# Steppers.net
KiCad netlist of a schematic drawn in Altium Designer
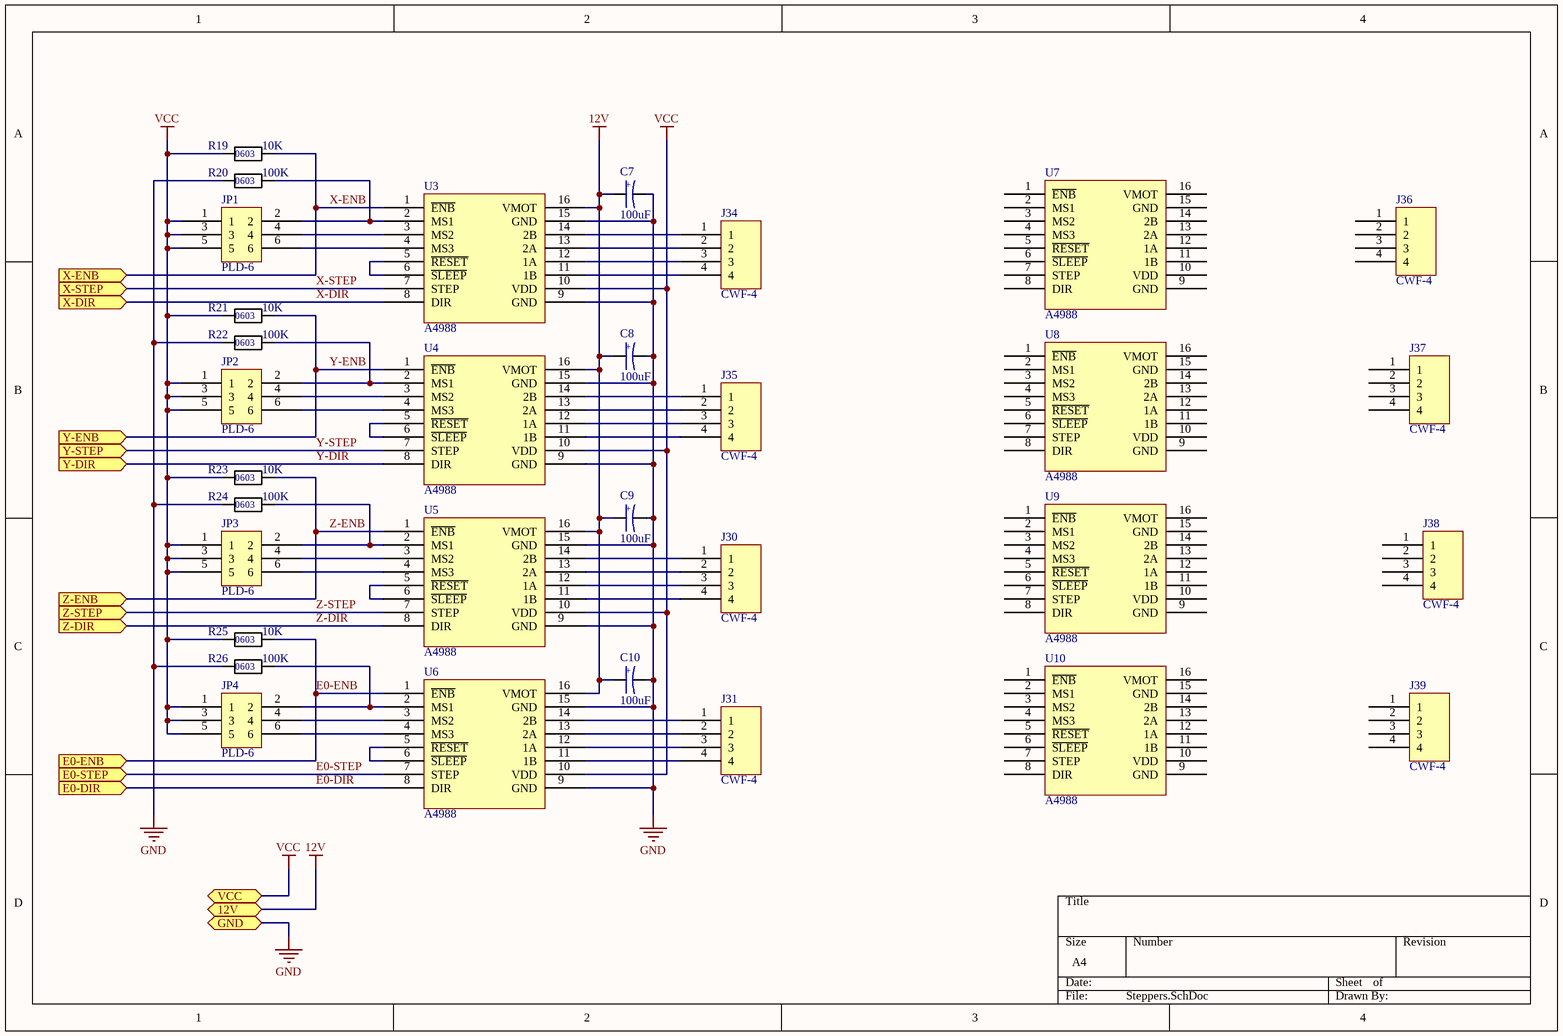
[diagram p0: Steppers.SchDoc]

(export (version "E")
  (design (tool "Eeschema 10.0.6"))
  (components
    (comp (ref "C7") (value "100uF") (footprint "Tantal - D") (libsource (lib "Popular") (part "Tantal")))
    (comp (ref "C8") (value "100uF") (footprint "Tantal - D") (libsource (lib "Popular") (part "Tantal")))
    (comp (ref "C9") (value "100uF") (footprint "Tantal - D") (libsource (lib "Popular") (part "Tantal")))
    (comp (ref "C10") (value "100uF") (footprint "Tantal - D") (libsource (lib "Popular") (part "Tantal")))
    (comp (ref "J30") (value "CWF-4") (footprint "CWF-4") (libsource (lib "Popular") (part "CWF-4")))
    (comp (ref "J31") (value "CWF-4") (footprint "CWF-4") (libsource (lib "Popular") (part "CWF-4")))
    (comp (ref "J34") (value "CWF-4") (footprint "CWF-4") (libsource (lib "Popular") (part "CWF-4")))
    (comp (ref "J35") (value "CWF-4") (footprint "CWF-4") (libsource (lib "Popular") (part "CWF-4")))
    (comp (ref "J36") (value "CWF-4") (footprint "CWF-4") (libsource (lib "Popular") (part "CWF-4")))
    (comp (ref "J37") (value "CWF-4") (footprint "CWF-4") (libsource (lib "Popular") (part "CWF-4")))
    (comp (ref "J38") (value "CWF-4") (footprint "CWF-4") (libsource (lib "Popular") (part "CWF-4")))
    (comp (ref "J39") (value "CWF-4") (footprint "CWF-4") (libsource (lib "Popular") (part "CWF-4")))
    (comp (ref "JP1") (value "PLD-6") (footprint "PLD-6") (libsource (lib "Popular") (part "PLD-6")))
    (comp (ref "JP2") (value "PLD-6") (footprint "PLD-6") (libsource (lib "Popular") (part "PLD-6")))
    (comp (ref "JP3") (value "PLD-6") (footprint "PLD-6") (libsource (lib "Popular") (part "PLD-6")))
    (comp (ref "JP4") (value "PLD-6") (footprint "PLD-6") (libsource (lib "Popular") (part "PLD-6")))
    (comp (ref "R19") (value "10K") (footprint "CHIP_R_0603") (libsource (lib "Popular") (part "RES_0603")))
    (comp (ref "R20") (value "100K") (footprint "CHIP_R_0603") (libsource (lib "Popular") (part "RES_0603")))
    (comp (ref "R21") (value "10K") (footprint "CHIP_R_0603") (libsource (lib "Popular") (part "RES_0603")))
    (comp (ref "R22") (value "100K") (footprint "CHIP_R_0603") (libsource (lib "Popular") (part "RES_0603")))
    (comp (ref "R23") (value "10K") (footprint "CHIP_R_0603") (libsource (lib "Popular") (part "RES_0603")))
    (comp (ref "R24") (value "100K") (footprint "CHIP_R_0603") (libsource (lib "Popular") (part "RES_0603")))
    (comp (ref "R25") (value "10K") (footprint "CHIP_R_0603") (libsource (lib "Popular") (part "RES_0603")))
    (comp (ref "R26") (value "100K") (footprint "CHIP_R_0603") (libsource (lib "Popular") (part "RES_0603")))
    (comp (ref "U3") (value "A4988") (footprint "A4988") (libsource (lib "Popular") (part "A4988_Carrier")))
    (comp (ref "U4") (value "A4988") (footprint "A4988") (libsource (lib "Popular") (part "A4988_Carrier")))
    (comp (ref "U5") (value "A4988") (footprint "A4988") (libsource (lib "Popular") (part "A4988_Carrier")))
    (comp (ref "U6") (value "A4988") (footprint "A4988") (libsource (lib "Popular") (part "A4988_Carrier")))
    (comp (ref "U7") (value "A4988") (footprint "A4988") (libsource (lib "Popular") (part "A4988_Carrier")))
    (comp (ref "U8") (value "A4988") (footprint "A4988") (libsource (lib "Popular") (part "A4988_Carrier")))
    (comp (ref "U9") (value "A4988") (footprint "A4988") (libsource (lib "Popular") (part "A4988_Carrier")))
    (comp (ref "U10") (value "A4988") (footprint "A4988") (libsource (lib "Popular") (part "A4988_Carrier")))
  )
  (nets
    (net (code "1") (name "/E0-DIR") (class "Default")
      (node (ref "U6") (pin "8") (pinfunction "DIR_8") (pintype "passive"))
    )
    (net (code "2") (name "/E0-ENB") (class "Default")
      (node (ref "R25") (pin "2") (pinfunction "2_2") (pintype "passive"))
      (node (ref "U6") (pin "1") (pinfunction "~{ENB}_1") (pintype "passive"))
    )
    (net (code "3") (name "/E0-STEP") (class "Default")
      (node (ref "U6") (pin "7") (pinfunction "STEP_7") (pintype "passive"))
    )
    (net (code "4") (name "/X-DIR") (class "Default")
      (node (ref "U3") (pin "8") (pinfunction "DIR_8") (pintype "passive"))
    )
    (net (code "5") (name "/X-ENB") (class "Default")
      (node (ref "R19") (pin "2") (pinfunction "2_2") (pintype "passive"))
      (node (ref "U3") (pin "1") (pinfunction "~{ENB}_1") (pintype "passive"))
    )
    (net (code "6") (name "/X-STEP") (class "Default")
      (node (ref "U3") (pin "7") (pinfunction "STEP_7") (pintype "passive"))
    )
    (net (code "7") (name "/Y-DIR") (class "Default")
      (node (ref "U4") (pin "8") (pinfunction "DIR_8") (pintype "passive"))
    )
    (net (code "8") (name "/Y-ENB") (class "Default")
      (node (ref "R21") (pin "2") (pinfunction "2_2") (pintype "passive"))
      (node (ref "U4") (pin "1") (pinfunction "~{ENB}_1") (pintype "passive"))
    )
    (net (code "9") (name "/Y-STEP") (class "Default")
      (node (ref "U4") (pin "7") (pinfunction "STEP_7") (pintype "passive"))
    )
    (net (code "10") (name "/Z-DIR") (class "Default")
      (node (ref "U5") (pin "8") (pinfunction "DIR_8") (pintype "passive"))
    )
    (net (code "11") (name "/Z-ENB") (class "Default")
      (node (ref "R23") (pin "2") (pinfunction "2_2") (pintype "passive"))
      (node (ref "U5") (pin "1") (pinfunction "~{ENB}_1") (pintype "passive"))
    )
    (net (code "12") (name "/Z-STEP") (class "Default")
      (node (ref "U5") (pin "7") (pinfunction "STEP_7") (pintype "passive"))
    )
    (net (code "13") (name "12V") (class "Default")
      (node (ref "C10") (pin "1") (pinfunction "1_1") (pintype "passive"))
      (node (ref "C7") (pin "1") (pinfunction "1_1") (pintype "passive"))
      (node (ref "C8") (pin "1") (pinfunction "1_1") (pintype "passive"))
      (node (ref "C9") (pin "1") (pinfunction "1_1") (pintype "passive"))
      (node (ref "U3") (pin "16") (pinfunction "VMOT_16") (pintype "passive"))
      (node (ref "U4") (pin "16") (pinfunction "VMOT_16") (pintype "passive"))
      (node (ref "U5") (pin "16") (pinfunction "VMOT_16") (pintype "passive"))
      (node (ref "U6") (pin "16") (pinfunction "VMOT_16") (pintype "passive"))
    )
    (net (code "14") (name "GND") (class "Default")
      (node (ref "C10") (pin "2") (pinfunction "2_2") (pintype "passive"))
      (node (ref "C7") (pin "2") (pinfunction "2_2") (pintype "passive"))
      (node (ref "C8") (pin "2") (pinfunction "2_2") (pintype "passive"))
      (node (ref "C9") (pin "2") (pinfunction "2_2") (pintype "passive"))
      (node (ref "R20") (pin "1") (pinfunction "1_1") (pintype "passive"))
      (node (ref "R22") (pin "1") (pinfunction "1_1") (pintype "passive"))
      (node (ref "R24") (pin "1") (pinfunction "1_1") (pintype "passive"))
      (node (ref "R26") (pin "1") (pinfunction "1_1") (pintype "passive"))
      (node (ref "U3") (pin "15") (pinfunction "GND_15") (pintype "passive"))
      (node (ref "U3") (pin "9") (pinfunction "GND_9") (pintype "passive"))
      (node (ref "U4") (pin "15") (pinfunction "GND_15") (pintype "passive"))
      (node (ref "U4") (pin "9") (pinfunction "GND_9") (pintype "passive"))
      (node (ref "U5") (pin "15") (pinfunction "GND_15") (pintype "passive"))
      (node (ref "U5") (pin "9") (pinfunction "GND_9") (pintype "passive"))
      (node (ref "U6") (pin "15") (pinfunction "GND_15") (pintype "passive"))
      (node (ref "U6") (pin "9") (pinfunction "GND_9") (pintype "passive"))
    )
    (net (code "15") (name "Net-(U3-1A)") (class "Default")
      (node (ref "J34") (pin "3") (pinfunction "3_3") (pintype "passive"))
      (node (ref "U3") (pin "12") (pinfunction "1A_12") (pintype "passive"))
    )
    (net (code "16") (name "Net-(U3-1B)") (class "Default")
      (node (ref "J34") (pin "4") (pinfunction "4_4") (pintype "passive"))
      (node (ref "U3") (pin "11") (pinfunction "1B_11") (pintype "passive"))
    )
    (net (code "17") (name "Net-(U3-2A)") (class "Default")
      (node (ref "J34") (pin "2") (pinfunction "2_2") (pintype "passive"))
      (node (ref "U3") (pin "13") (pinfunction "2A_13") (pintype "passive"))
    )
    (net (code "18") (name "Net-(U3-2B)") (class "Default")
      (node (ref "J34") (pin "1") (pinfunction "1_1") (pintype "passive"))
      (node (ref "U3") (pin "14") (pinfunction "2B_14") (pintype "passive"))
    )
    (net (code "19") (name "Net-(U3-MS1)") (class "Default")
      (node (ref "JP1") (pin "2") (pinfunction "2_2") (pintype "passive"))
      (node (ref "R20") (pin "2") (pinfunction "2_2") (pintype "passive"))
      (node (ref "U3") (pin "2") (pinfunction "MS1_2") (pintype "passive"))
    )
    (net (code "20") (name "Net-(U3-MS2)") (class "Default")
      (node (ref "JP1") (pin "4") (pinfunction "4_4") (pintype "passive"))
      (node (ref "U3") (pin "3") (pinfunction "MS2_3") (pintype "passive"))
    )
    (net (code "21") (name "Net-(U3-MS3)") (class "Default")
      (node (ref "JP1") (pin "6") (pinfunction "6_6") (pintype "passive"))
      (node (ref "U3") (pin "4") (pinfunction "MS3_4") (pintype "passive"))
    )
    (net (code "22") (name "Net-(U3-~{RESET})") (class "Default")
      (node (ref "U3") (pin "5") (pinfunction "~{RESET}_5") (pintype "passive"))
      (node (ref "U3") (pin "6") (pinfunction "~{SLEEP}_6") (pintype "passive"))
    )
    (net (code "23") (name "Net-(U4-1A)") (class "Default")
      (node (ref "J35") (pin "3") (pinfunction "3_3") (pintype "passive"))
      (node (ref "U4") (pin "12") (pinfunction "1A_12") (pintype "passive"))
    )
    (net (code "24") (name "Net-(U4-1B)") (class "Default")
      (node (ref "J35") (pin "4") (pinfunction "4_4") (pintype "passive"))
      (node (ref "U4") (pin "11") (pinfunction "1B_11") (pintype "passive"))
    )
    (net (code "25") (name "Net-(U4-2A)") (class "Default")
      (node (ref "J35") (pin "2") (pinfunction "2_2") (pintype "passive"))
      (node (ref "U4") (pin "13") (pinfunction "2A_13") (pintype "passive"))
    )
    (net (code "26") (name "Net-(U4-2B)") (class "Default")
      (node (ref "J35") (pin "1") (pinfunction "1_1") (pintype "passive"))
      (node (ref "U4") (pin "14") (pinfunction "2B_14") (pintype "passive"))
    )
    (net (code "27") (name "Net-(U4-MS1)") (class "Default")
      (node (ref "JP2") (pin "2") (pinfunction "2_2") (pintype "passive"))
      (node (ref "R22") (pin "2") (pinfunction "2_2") (pintype "passive"))
      (node (ref "U4") (pin "2") (pinfunction "MS1_2") (pintype "passive"))
    )
    (net (code "28") (name "Net-(U4-MS2)") (class "Default")
      (node (ref "JP2") (pin "4") (pinfunction "4_4") (pintype "passive"))
      (node (ref "U4") (pin "3") (pinfunction "MS2_3") (pintype "passive"))
    )
    (net (code "29") (name "Net-(U4-MS3)") (class "Default")
      (node (ref "JP2") (pin "6") (pinfunction "6_6") (pintype "passive"))
      (node (ref "U4") (pin "4") (pinfunction "MS3_4") (pintype "passive"))
    )
    (net (code "30") (name "Net-(U4-~{RESET})") (class "Default")
      (node (ref "U4") (pin "5") (pinfunction "~{RESET}_5") (pintype "passive"))
      (node (ref "U4") (pin "6") (pinfunction "~{SLEEP}_6") (pintype "passive"))
    )
    (net (code "31") (name "Net-(U5-1A)") (class "Default")
      (node (ref "J30") (pin "3") (pinfunction "3_3") (pintype "passive"))
      (node (ref "U5") (pin "12") (pinfunction "1A_12") (pintype "passive"))
    )
    (net (code "32") (name "Net-(U5-1B)") (class "Default")
      (node (ref "J30") (pin "4") (pinfunction "4_4") (pintype "passive"))
      (node (ref "U5") (pin "11") (pinfunction "1B_11") (pintype "passive"))
    )
    (net (code "33") (name "Net-(U5-2A)") (class "Default")
      (node (ref "J30") (pin "2") (pinfunction "2_2") (pintype "passive"))
      (node (ref "U5") (pin "13") (pinfunction "2A_13") (pintype "passive"))
    )
    (net (code "34") (name "Net-(U5-2B)") (class "Default")
      (node (ref "J30") (pin "1") (pinfunction "1_1") (pintype "passive"))
      (node (ref "U5") (pin "14") (pinfunction "2B_14") (pintype "passive"))
    )
    (net (code "35") (name "Net-(U5-MS1)") (class "Default")
      (node (ref "JP3") (pin "2") (pinfunction "2_2") (pintype "passive"))
      (node (ref "R24") (pin "2") (pinfunction "2_2") (pintype "passive"))
      (node (ref "U5") (pin "2") (pinfunction "MS1_2") (pintype "passive"))
    )
    (net (code "36") (name "Net-(U5-MS2)") (class "Default")
      (node (ref "JP3") (pin "4") (pinfunction "4_4") (pintype "passive"))
      (node (ref "U5") (pin "3") (pinfunction "MS2_3") (pintype "passive"))
    )
    (net (code "37") (name "Net-(U5-MS3)") (class "Default")
      (node (ref "JP3") (pin "6") (pinfunction "6_6") (pintype "passive"))
      (node (ref "U5") (pin "4") (pinfunction "MS3_4") (pintype "passive"))
    )
    (net (code "38") (name "Net-(U5-~{RESET})") (class "Default")
      (node (ref "U5") (pin "5") (pinfunction "~{RESET}_5") (pintype "passive"))
      (node (ref "U5") (pin "6") (pinfunction "~{SLEEP}_6") (pintype "passive"))
    )
    (net (code "39") (name "Net-(U6-1A)") (class "Default")
      (node (ref "J31") (pin "3") (pinfunction "3_3") (pintype "passive"))
      (node (ref "U6") (pin "12") (pinfunction "1A_12") (pintype "passive"))
    )
    (net (code "40") (name "Net-(U6-1B)") (class "Default")
      (node (ref "J31") (pin "4") (pinfunction "4_4") (pintype "passive"))
      (node (ref "U6") (pin "11") (pinfunction "1B_11") (pintype "passive"))
    )
    (net (code "41") (name "Net-(U6-2A)") (class "Default")
      (node (ref "J31") (pin "2") (pinfunction "2_2") (pintype "passive"))
      (node (ref "U6") (pin "13") (pinfunction "2A_13") (pintype "passive"))
    )
    (net (code "42") (name "Net-(U6-2B)") (class "Default")
      (node (ref "J31") (pin "1") (pinfunction "1_1") (pintype "passive"))
      (node (ref "U6") (pin "14") (pinfunction "2B_14") (pintype "passive"))
    )
    (net (code "43") (name "Net-(U6-MS1)") (class "Default")
      (node (ref "JP4") (pin "2") (pinfunction "2_2") (pintype "passive"))
      (node (ref "R26") (pin "2") (pinfunction "2_2") (pintype "passive"))
      (node (ref "U6") (pin "2") (pinfunction "MS1_2") (pintype "passive"))
    )
    (net (code "44") (name "Net-(U6-MS2)") (class "Default")
      (node (ref "JP4") (pin "4") (pinfunction "4_4") (pintype "passive"))
      (node (ref "U6") (pin "3") (pinfunction "MS2_3") (pintype "passive"))
    )
    (net (code "45") (name "Net-(U6-MS3)") (class "Default")
      (node (ref "JP4") (pin "6") (pinfunction "6_6") (pintype "passive"))
      (node (ref "U6") (pin "4") (pinfunction "MS3_4") (pintype "passive"))
    )
    (net (code "46") (name "Net-(U6-~{RESET})") (class "Default")
      (node (ref "U6") (pin "5") (pinfunction "~{RESET}_5") (pintype "passive"))
      (node (ref "U6") (pin "6") (pinfunction "~{SLEEP}_6") (pintype "passive"))
    )
    (net (code "47") (name "VCC") (class "Default")
      (node (ref "JP1") (pin "1") (pinfunction "1_1") (pintype "passive"))
      (node (ref "JP1") (pin "3") (pinfunction "3_3") (pintype "passive"))
      (node (ref "JP1") (pin "5") (pinfunction "5_5") (pintype "passive"))
      (node (ref "JP2") (pin "1") (pinfunction "1_1") (pintype "passive"))
      (node (ref "JP2") (pin "3") (pinfunction "3_3") (pintype "passive"))
      (node (ref "JP2") (pin "5") (pinfunction "5_5") (pintype "passive"))
      (node (ref "JP3") (pin "1") (pinfunction "1_1") (pintype "passive"))
      (node (ref "JP3") (pin "3") (pinfunction "3_3") (pintype "passive"))
      (node (ref "JP3") (pin "5") (pinfunction "5_5") (pintype "passive"))
      (node (ref "JP4") (pin "1") (pinfunction "1_1") (pintype "passive"))
      (node (ref "JP4") (pin "3") (pinfunction "3_3") (pintype "passive"))
      (node (ref "JP4") (pin "5") (pinfunction "5_5") (pintype "passive"))
      (node (ref "R19") (pin "1") (pinfunction "1_1") (pintype "passive"))
      (node (ref "R21") (pin "1") (pinfunction "1_1") (pintype "passive"))
      (node (ref "R23") (pin "1") (pinfunction "1_1") (pintype "passive"))
      (node (ref "R25") (pin "1") (pinfunction "1_1") (pintype "passive"))
      (node (ref "U3") (pin "10") (pinfunction "VDD_10") (pintype "passive"))
      (node (ref "U4") (pin "10") (pinfunction "VDD_10") (pintype "passive"))
      (node (ref "U5") (pin "10") (pinfunction "VDD_10") (pintype "passive"))
      (node (ref "U6") (pin "10") (pinfunction "VDD_10") (pintype "passive"))
    )
    (net (code "48") (name "unconnected-(J36-Pad1)") (class "Default")
      (node (ref "J36") (pin "1") (pinfunction "1_1") (pintype "passive"))
    )
    (net (code "49") (name "unconnected-(J36-Pad2)") (class "Default")
      (node (ref "J36") (pin "2") (pinfunction "2_2") (pintype "passive"))
    )
    (net (code "50") (name "unconnected-(J36-Pad3)") (class "Default")
      (node (ref "J36") (pin "3") (pinfunction "3_3") (pintype "passive"))
    )
    (net (code "51") (name "unconnected-(J36-Pad4)") (class "Default")
      (node (ref "J36") (pin "4") (pinfunction "4_4") (pintype "passive"))
    )
    (net (code "52") (name "unconnected-(J37-Pad1)") (class "Default")
      (node (ref "J37") (pin "1") (pinfunction "1_1") (pintype "passive"))
    )
    (net (code "53") (name "unconnected-(J37-Pad2)") (class "Default")
      (node (ref "J37") (pin "2") (pinfunction "2_2") (pintype "passive"))
    )
    (net (code "54") (name "unconnected-(J37-Pad3)") (class "Default")
      (node (ref "J37") (pin "3") (pinfunction "3_3") (pintype "passive"))
    )
    (net (code "55") (name "unconnected-(J37-Pad4)") (class "Default")
      (node (ref "J37") (pin "4") (pinfunction "4_4") (pintype "passive"))
    )
    (net (code "56") (name "unconnected-(J38-Pad1)") (class "Default")
      (node (ref "J38") (pin "1") (pinfunction "1_1") (pintype "passive"))
    )
    (net (code "57") (name "unconnected-(J38-Pad2)") (class "Default")
      (node (ref "J38") (pin "2") (pinfunction "2_2") (pintype "passive"))
    )
    (net (code "58") (name "unconnected-(J38-Pad3)") (class "Default")
      (node (ref "J38") (pin "3") (pinfunction "3_3") (pintype "passive"))
    )
    (net (code "59") (name "unconnected-(J38-Pad4)") (class "Default")
      (node (ref "J38") (pin "4") (pinfunction "4_4") (pintype "passive"))
    )
    (net (code "60") (name "unconnected-(J39-Pad1)") (class "Default")
      (node (ref "J39") (pin "1") (pinfunction "1_1") (pintype "passive"))
    )
    (net (code "61") (name "unconnected-(J39-Pad2)") (class "Default")
      (node (ref "J39") (pin "2") (pinfunction "2_2") (pintype "passive"))
    )
    (net (code "62") (name "unconnected-(J39-Pad3)") (class "Default")
      (node (ref "J39") (pin "3") (pinfunction "3_3") (pintype "passive"))
    )
    (net (code "63") (name "unconnected-(J39-Pad4)") (class "Default")
      (node (ref "J39") (pin "4") (pinfunction "4_4") (pintype "passive"))
    )
    (net (code "64") (name "unconnected-(U7-1A-Pad12)") (class "Default")
      (node (ref "U7") (pin "12") (pinfunction "1A_12") (pintype "passive"))
    )
    (net (code "65") (name "unconnected-(U7-1B-Pad11)") (class "Default")
      (node (ref "U7") (pin "11") (pinfunction "1B_11") (pintype "passive"))
    )
    (net (code "66") (name "unconnected-(U7-2A-Pad13)") (class "Default")
      (node (ref "U7") (pin "13") (pinfunction "2A_13") (pintype "passive"))
    )
    (net (code "67") (name "unconnected-(U7-2B-Pad14)") (class "Default")
      (node (ref "U7") (pin "14") (pinfunction "2B_14") (pintype "passive"))
    )
    (net (code "68") (name "unconnected-(U7-DIR-Pad8)") (class "Default")
      (node (ref "U7") (pin "8") (pinfunction "DIR_8") (pintype "passive"))
    )
    (net (code "69") (name "unconnected-(U7-GND-Pad9)") (class "Default")
      (node (ref "U7") (pin "9") (pinfunction "GND_9") (pintype "passive"))
    )
    (net (code "70") (name "unconnected-(U7-GND-Pad15)") (class "Default")
      (node (ref "U7") (pin "15") (pinfunction "GND_15") (pintype "passive"))
    )
    (net (code "71") (name "unconnected-(U7-MS1-Pad2)") (class "Default")
      (node (ref "U7") (pin "2") (pinfunction "MS1_2") (pintype "passive"))
    )
    (net (code "72") (name "unconnected-(U7-MS2-Pad3)") (class "Default")
      (node (ref "U7") (pin "3") (pinfunction "MS2_3") (pintype "passive"))
    )
    (net (code "73") (name "unconnected-(U7-MS3-Pad4)") (class "Default")
      (node (ref "U7") (pin "4") (pinfunction "MS3_4") (pintype "passive"))
    )
    (net (code "74") (name "unconnected-(U7-STEP-Pad7)") (class "Default")
      (node (ref "U7") (pin "7") (pinfunction "STEP_7") (pintype "passive"))
    )
    (net (code "75") (name "unconnected-(U7-VDD-Pad10)") (class "Default")
      (node (ref "U7") (pin "10") (pinfunction "VDD_10") (pintype "passive"))
    )
    (net (code "76") (name "unconnected-(U7-VMOT-Pad16)") (class "Default")
      (node (ref "U7") (pin "16") (pinfunction "VMOT_16") (pintype "passive"))
    )
    (net (code "77") (name "unconnected-(U7-~{ENB}-Pad1)") (class "Default")
      (node (ref "U7") (pin "1") (pinfunction "~{ENB}_1") (pintype "passive"))
    )
    (net (code "78") (name "unconnected-(U7-~{RESET}-Pad5)") (class "Default")
      (node (ref "U7") (pin "5") (pinfunction "~{RESET}_5") (pintype "passive"))
    )
    (net (code "79") (name "unconnected-(U7-~{SLEEP}-Pad6)") (class "Default")
      (node (ref "U7") (pin "6") (pinfunction "~{SLEEP}_6") (pintype "passive"))
    )
    (net (code "80") (name "unconnected-(U8-1A-Pad12)") (class "Default")
      (node (ref "U8") (pin "12") (pinfunction "1A_12") (pintype "passive"))
    )
    (net (code "81") (name "unconnected-(U8-1B-Pad11)") (class "Default")
      (node (ref "U8") (pin "11") (pinfunction "1B_11") (pintype "passive"))
    )
    (net (code "82") (name "unconnected-(U8-2A-Pad13)") (class "Default")
      (node (ref "U8") (pin "13") (pinfunction "2A_13") (pintype "passive"))
    )
    (net (code "83") (name "unconnected-(U8-2B-Pad14)") (class "Default")
      (node (ref "U8") (pin "14") (pinfunction "2B_14") (pintype "passive"))
    )
    (net (code "84") (name "unconnected-(U8-DIR-Pad8)") (class "Default")
      (node (ref "U8") (pin "8") (pinfunction "DIR_8") (pintype "passive"))
    )
    (net (code "85") (name "unconnected-(U8-GND-Pad9)") (class "Default")
      (node (ref "U8") (pin "9") (pinfunction "GND_9") (pintype "passive"))
    )
    (net (code "86") (name "unconnected-(U8-GND-Pad15)") (class "Default")
      (node (ref "U8") (pin "15") (pinfunction "GND_15") (pintype "passive"))
    )
    (net (code "87") (name "unconnected-(U8-MS1-Pad2)") (class "Default")
      (node (ref "U8") (pin "2") (pinfunction "MS1_2") (pintype "passive"))
    )
    (net (code "88") (name "unconnected-(U8-MS2-Pad3)") (class "Default")
      (node (ref "U8") (pin "3") (pinfunction "MS2_3") (pintype "passive"))
    )
    (net (code "89") (name "unconnected-(U8-MS3-Pad4)") (class "Default")
      (node (ref "U8") (pin "4") (pinfunction "MS3_4") (pintype "passive"))
    )
    (net (code "90") (name "unconnected-(U8-STEP-Pad7)") (class "Default")
      (node (ref "U8") (pin "7") (pinfunction "STEP_7") (pintype "passive"))
    )
    (net (code "91") (name "unconnected-(U8-VDD-Pad10)") (class "Default")
      (node (ref "U8") (pin "10") (pinfunction "VDD_10") (pintype "passive"))
    )
    (net (code "92") (name "unconnected-(U8-VMOT-Pad16)") (class "Default")
      (node (ref "U8") (pin "16") (pinfunction "VMOT_16") (pintype "passive"))
    )
    (net (code "93") (name "unconnected-(U8-~{ENB}-Pad1)") (class "Default")
      (node (ref "U8") (pin "1") (pinfunction "~{ENB}_1") (pintype "passive"))
    )
    (net (code "94") (name "unconnected-(U8-~{RESET}-Pad5)") (class "Default")
      (node (ref "U8") (pin "5") (pinfunction "~{RESET}_5") (pintype "passive"))
    )
    (net (code "95") (name "unconnected-(U8-~{SLEEP}-Pad6)") (class "Default")
      (node (ref "U8") (pin "6") (pinfunction "~{SLEEP}_6") (pintype "passive"))
    )
    (net (code "96") (name "unconnected-(U9-1A-Pad12)") (class "Default")
      (node (ref "U9") (pin "12") (pinfunction "1A_12") (pintype "passive"))
    )
    (net (code "97") (name "unconnected-(U9-1B-Pad11)") (class "Default")
      (node (ref "U9") (pin "11") (pinfunction "1B_11") (pintype "passive"))
    )
    (net (code "98") (name "unconnected-(U9-2A-Pad13)") (class "Default")
      (node (ref "U9") (pin "13") (pinfunction "2A_13") (pintype "passive"))
    )
    (net (code "99") (name "unconnected-(U9-2B-Pad14)") (class "Default")
      (node (ref "U9") (pin "14") (pinfunction "2B_14") (pintype "passive"))
    )
    (net (code "100") (name "unconnected-(U9-DIR-Pad8)") (class "Default")
      (node (ref "U9") (pin "8") (pinfunction "DIR_8") (pintype "passive"))
    )
    (net (code "101") (name "unconnected-(U9-GND-Pad9)") (class "Default")
      (node (ref "U9") (pin "9") (pinfunction "GND_9") (pintype "passive"))
    )
    (net (code "102") (name "unconnected-(U9-GND-Pad15)") (class "Default")
      (node (ref "U9") (pin "15") (pinfunction "GND_15") (pintype "passive"))
    )
    (net (code "103") (name "unconnected-(U9-MS1-Pad2)") (class "Default")
      (node (ref "U9") (pin "2") (pinfunction "MS1_2") (pintype "passive"))
    )
    (net (code "104") (name "unconnected-(U9-MS2-Pad3)") (class "Default")
      (node (ref "U9") (pin "3") (pinfunction "MS2_3") (pintype "passive"))
    )
    (net (code "105") (name "unconnected-(U9-MS3-Pad4)") (class "Default")
      (node (ref "U9") (pin "4") (pinfunction "MS3_4") (pintype "passive"))
    )
    (net (code "106") (name "unconnected-(U9-STEP-Pad7)") (class "Default")
      (node (ref "U9") (pin "7") (pinfunction "STEP_7") (pintype "passive"))
    )
    (net (code "107") (name "unconnected-(U9-VDD-Pad10)") (class "Default")
      (node (ref "U9") (pin "10") (pinfunction "VDD_10") (pintype "passive"))
    )
    (net (code "108") (name "unconnected-(U9-VMOT-Pad16)") (class "Default")
      (node (ref "U9") (pin "16") (pinfunction "VMOT_16") (pintype "passive"))
    )
    (net (code "109") (name "unconnected-(U9-~{ENB}-Pad1)") (class "Default")
      (node (ref "U9") (pin "1") (pinfunction "~{ENB}_1") (pintype "passive"))
    )
    (net (code "110") (name "unconnected-(U9-~{RESET}-Pad5)") (class "Default")
      (node (ref "U9") (pin "5") (pinfunction "~{RESET}_5") (pintype "passive"))
    )
    (net (code "111") (name "unconnected-(U9-~{SLEEP}-Pad6)") (class "Default")
      (node (ref "U9") (pin "6") (pinfunction "~{SLEEP}_6") (pintype "passive"))
    )
    (net (code "112") (name "unconnected-(U10-1A-Pad12)") (class "Default")
      (node (ref "U10") (pin "12") (pinfunction "1A_12") (pintype "passive"))
    )
    (net (code "113") (name "unconnected-(U10-1B-Pad11)") (class "Default")
      (node (ref "U10") (pin "11") (pinfunction "1B_11") (pintype "passive"))
    )
    (net (code "114") (name "unconnected-(U10-2A-Pad13)") (class "Default")
      (node (ref "U10") (pin "13") (pinfunction "2A_13") (pintype "passive"))
    )
    (net (code "115") (name "unconnected-(U10-2B-Pad14)") (class "Default")
      (node (ref "U10") (pin "14") (pinfunction "2B_14") (pintype "passive"))
    )
    (net (code "116") (name "unconnected-(U10-DIR-Pad8)") (class "Default")
      (node (ref "U10") (pin "8") (pinfunction "DIR_8") (pintype "passive"))
    )
    (net (code "117") (name "unconnected-(U10-GND-Pad9)") (class "Default")
      (node (ref "U10") (pin "9") (pinfunction "GND_9") (pintype "passive"))
    )
    (net (code "118") (name "unconnected-(U10-GND-Pad15)") (class "Default")
      (node (ref "U10") (pin "15") (pinfunction "GND_15") (pintype "passive"))
    )
    (net (code "119") (name "unconnected-(U10-MS1-Pad2)") (class "Default")
      (node (ref "U10") (pin "2") (pinfunction "MS1_2") (pintype "passive"))
    )
    (net (code "120") (name "unconnected-(U10-MS2-Pad3)") (class "Default")
      (node (ref "U10") (pin "3") (pinfunction "MS2_3") (pintype "passive"))
    )
    (net (code "121") (name "unconnected-(U10-MS3-Pad4)") (class "Default")
      (node (ref "U10") (pin "4") (pinfunction "MS3_4") (pintype "passive"))
    )
    (net (code "122") (name "unconnected-(U10-STEP-Pad7)") (class "Default")
      (node (ref "U10") (pin "7") (pinfunction "STEP_7") (pintype "passive"))
    )
    (net (code "123") (name "unconnected-(U10-VDD-Pad10)") (class "Default")
      (node (ref "U10") (pin "10") (pinfunction "VDD_10") (pintype "passive"))
    )
    (net (code "124") (name "unconnected-(U10-VMOT-Pad16)") (class "Default")
      (node (ref "U10") (pin "16") (pinfunction "VMOT_16") (pintype "passive"))
    )
    (net (code "125") (name "unconnected-(U10-~{ENB}-Pad1)") (class "Default")
      (node (ref "U10") (pin "1") (pinfunction "~{ENB}_1") (pintype "passive"))
    )
    (net (code "126") (name "unconnected-(U10-~{RESET}-Pad5)") (class "Default")
      (node (ref "U10") (pin "5") (pinfunction "~{RESET}_5") (pintype "passive"))
    )
    (net (code "127") (name "unconnected-(U10-~{SLEEP}-Pad6)") (class "Default")
      (node (ref "U10") (pin "6") (pinfunction "~{SLEEP}_6") (pintype "passive"))
    )
  )
)
